# schematics.net
KiCad netlist of a schematic drawn in EAGLE
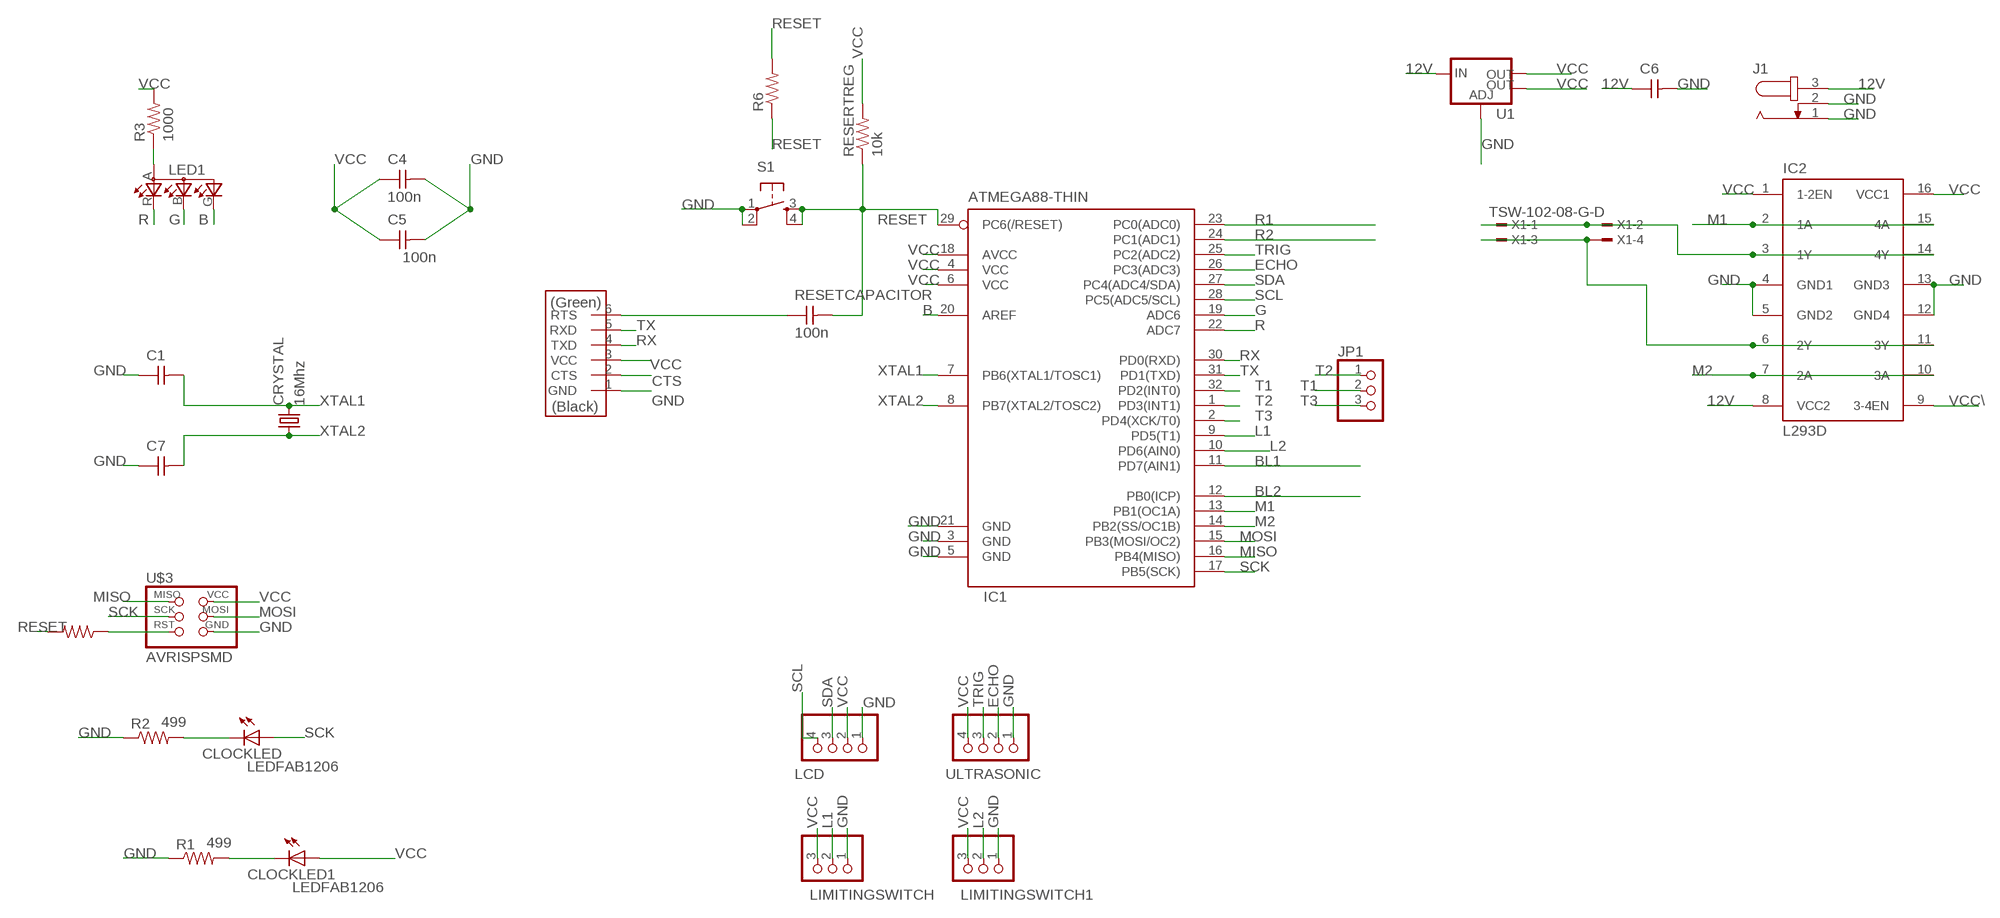
[diagram p0: schematic, sheet 1]

(export (version "E")
  (design (tool "Eeschema 10.0.6"))
  (components
    (comp (ref "C1")
      (value "CAP-UNPOLARIZEDFAB")
      (footprint "eagle-import:C1206FAB")
      (libsource (lib "eagle-import") (part "CAP-UNPOLARIZEDFAB"))
    )
    (comp (ref "C4")
      (value "100n")
      (footprint "eagle-import:C1206FAB")
      (libsource (lib "eagle-import") (part "CAP-UNPOLARIZEDFAB"))
    )
    (comp (ref "C5")
      (value "100n")
      (footprint "eagle-import:C1206FAB")
      (libsource (lib "eagle-import") (part "CAP-UNPOLARIZEDFAB"))
    )
    (comp (ref "C6")
      (value "CAP-UNPOLARIZEDFAB")
      (footprint "eagle-import:C1206FAB")
      (libsource (lib "eagle-import") (part "CAP-UNPOLARIZEDFAB"))
    )
    (comp (ref "C7")
      (value "CAP-UNPOLARIZEDFAB")
      (footprint "eagle-import:C1206FAB")
      (libsource (lib "eagle-import") (part "CAP-UNPOLARIZEDFAB"))
    )
    (comp (ref "CLOCKLED")
      (value "LEDFAB1206")
      (footprint "eagle-import:LED1206FAB")
      (libsource (lib "eagle-import") (part "LEDFAB1206"))
    )
    (comp (ref "CLOCKLED1")
      (value "LEDFAB1206")
      (footprint "eagle-import:LED1206FAB")
      (libsource (lib "eagle-import") (part "LEDFAB1206"))
    )
    (comp (ref "CRYSTAL")
      (value "16Mhz")
      (footprint "eagle-import:CSM-7X-DU")
      (libsource (lib "eagle-import") (part "CSM-7X-DU"))
    )
    (comp (ref "IC1")
      (value "ATMEGA88-THIN")
      (footprint "eagle-import:TQFP32-08THIN")
      (libsource (lib "eagle-import") (part "ATMEGA88-THIN"))
    )
    (comp (ref "IC2")
      (value "L293D")
      (footprint "eagle-import:DIL16")
      (libsource (lib "eagle-import") (part "L293D"))
    )
    (comp (ref "J1")
      (value "JACK-PLUG1")
      (footprint "eagle-import:SPC4078")
      (libsource (lib "eagle-import") (part "JACK-PLUG1"))
    )
    (comp (ref "JP1")
      (value "PINHD-1X31X03_SMT")
      (footprint "eagle-import:1X03_SMT")
      (libsource (lib "eagle-import") (part "PINHD-1X31X03_SMT"))
    )
    (comp (ref "LCD")
      (value "PINHD-1X41X04_SMT")
      (footprint "eagle-import:1X04_SMT")
      (libsource (lib "eagle-import") (part "PINHD-1X41X04_SMT"))
    )
    (comp (ref "LED1")
      (value "LEDRGBOLD")
      (footprint "eagle-import:P-LCC-4-3")
      (libsource (lib "eagle-import") (part "LEDRGBOLD"))
    )
    (comp (ref "LIMITINGSWITCH")
      (value "PINHD-1X31X03_SMT")
      (footprint "eagle-import:1X03_SMT")
      (libsource (lib "eagle-import") (part "PINHD-1X31X03_SMT"))
    )
    (comp (ref "LIMITINGSWITCH1")
      (value "PINHD-1X31X03_SMT")
      (footprint "eagle-import:1X03_SMT")
      (libsource (lib "eagle-import") (part "PINHD-1X31X03_SMT"))
    )
    (comp (ref "R1")
      (value "499")
      (footprint "eagle-import:R1206FAB")
      (libsource (lib "eagle-import") (part "RES-US1206FAB"))
    )
    (comp (ref "R2")
      (value "499")
      (footprint "eagle-import:R1206FAB")
      (libsource (lib "eagle-import") (part "RES-US1206FAB"))
    )
    (comp (ref "R3")
      (value "1000")
      (footprint "eagle-import:R1206FAB")
      (libsource (lib "eagle-import") (part "RES-US1206FAB"))
    )
    (comp (ref "R4")
      (value "1000")
      (footprint "eagle-import:R1206FAB")
      (libsource (lib "eagle-import") (part "RES-US1206FAB"))
    )
    (comp (ref "R6")
      (value "1000")
      (footprint "eagle-import:R1206FAB")
      (libsource (lib "eagle-import") (part "RES-US1206FAB"))
    )
    (comp (ref "RESERTREG")
      (value "10k")
      (footprint "eagle-import:R1206FAB")
      (libsource (lib "eagle-import") (part "RES-US1206FAB"))
    )
    (comp (ref "RESETCAPACITOR")
      (value "100n")
      (footprint "eagle-import:C1206FAB")
      (libsource (lib "eagle-import") (part "CAP-UNPOLARIZEDFAB"))
    )
    (comp (ref "S1")
      (value "6MM_SWITCH6MM_SWITCH")
      (footprint "eagle-import:6MM_SWITCH")
      (libsource (lib "eagle-import") (part "6MM_SWITCH6MM_SWITCH"))
    )
    (comp (ref "U$2")
      (value "FTDI-SMD-HEADER")
      (footprint "eagle-import:1X06SMD")
      (libsource (lib "eagle-import") (part "FTDI-SMD-HEADER"))
    )
    (comp (ref "U$3")
      (value "AVRISPSMD")
      (footprint "eagle-import:2X03SMD")
      (libsource (lib "eagle-import") (part "AVRISPSMD"))
    )
    (comp (ref "U1")
      (value "V_REG_LM1117SOT223")
      (footprint "eagle-import:SOT223")
      (libsource (lib "eagle-import") (part "V_REG_LM1117SOT223"))
    )
    (comp (ref "ULTRASONIC")
      (value "PINHD-1X41X04_SMT")
      (footprint "eagle-import:1X04_SMT")
      (libsource (lib "eagle-import") (part "PINHD-1X41X04_SMT"))
    )
    (comp (ref "X1")
      (value "TSW-102-08-G-D")
      (footprint "eagle-import:TSW-102-XX-G-D")
      (fields (field (name "MF") "Samtec Inc.") (field (name "MPN") "TSW-102-07-G-D"))
      (libsource (lib "eagle-import") (part "TSW-102--G-D08"))
    )
  )
  (nets
    (net (code "1") (name "/12V") (class "Default")
      (node (ref "C6") (pin "1") (pinfunction "1_1") (pintype "passive"))
      (node (ref "IC2") (pin "8") (pinfunction "VCC2_8") (pintype "power_in"))
      (node (ref "J1") (pin "3") (pinfunction "3_3") (pintype "passive"))
      (node (ref "U1") (pin "3") (pinfunction "IN_3") (pintype "input"))
    )
    (net (code "2") (name "/B") (class "Default")
      (node (ref "IC1") (pin "20") (pinfunction "AREF_20") (pintype "passive"))
      (node (ref "LED1") (pin "G") (pinfunction "CGREEN_G") (pintype "passive"))
    )
    (net (code "3") (name "/BL1") (class "Default")
      (node (ref "IC1") (pin "11") (pinfunction "PD7(AIN1)_11") (pintype "bidirectional"))
    )
    (net (code "4") (name "/BL2") (class "Default")
      (node (ref "IC1") (pin "12") (pinfunction "PB0(ICP)_12") (pintype "bidirectional"))
    )
    (net (code "5") (name "/CTS") (class "Default")
      (node (ref "U$2") (pin "2") (pinfunction "CTS_2") (pintype "bidirectional"))
    )
    (net (code "6") (name "/ECHO") (class "Default")
      (node (ref "IC1") (pin "26") (pinfunction "PC3(ADC3)_26") (pintype "bidirectional"))
      (node (ref "ULTRASONIC") (pin "2") (pinfunction "2_2") (pintype "passive"))
    )
    (net (code "7") (name "/G") (class "Default")
      (node (ref "IC1") (pin "19") (pinfunction "ADC6_19") (pintype "bidirectional"))
      (node (ref "LED1") (pin "B") (pinfunction "CBLUE_B") (pintype "passive"))
    )
    (net (code "8") (name "/GND") (class "Default")
      (node (ref "C1") (pin "1") (pinfunction "1_1") (pintype "passive"))
      (node (ref "C4") (pin "2") (pinfunction "2_2") (pintype "passive"))
      (node (ref "C5") (pin "2") (pinfunction "2_2") (pintype "passive"))
      (node (ref "C6") (pin "2") (pinfunction "2_2") (pintype "passive"))
      (node (ref "C7") (pin "1") (pinfunction "1_1") (pintype "passive"))
      (node (ref "IC1") (pin "21") (pinfunction "GND_21") (pintype "power_in"))
      (node (ref "IC1") (pin "3") (pinfunction "GND_3") (pintype "power_in"))
      (node (ref "IC1") (pin "5") (pinfunction "GND_5") (pintype "power_in"))
      (node (ref "IC2") (pin "12") (pinfunction "GND4_12") (pintype "power_in"))
      (node (ref "IC2") (pin "13") (pinfunction "GND3_13") (pintype "power_in"))
      (node (ref "IC2") (pin "4") (pinfunction "GND1_4") (pintype "power_in"))
      (node (ref "IC2") (pin "5") (pinfunction "GND2_5") (pintype "power_in"))
      (node (ref "J1") (pin "1") (pinfunction "1_1") (pintype "passive"))
      (node (ref "J1") (pin "2") (pinfunction "2_2") (pintype "passive"))
      (node (ref "LCD") (pin "1") (pinfunction "1_1") (pintype "passive"))
      (node (ref "LIMITINGSWITCH") (pin "1") (pinfunction "1_1") (pintype "passive"))
      (node (ref "LIMITINGSWITCH1") (pin "1") (pinfunction "1_1") (pintype "passive"))
      (node (ref "R1") (pin "1") (pinfunction "1_1") (pintype "passive"))
      (node (ref "R2") (pin "1") (pinfunction "1_1") (pintype "passive"))
      (node (ref "S1") (pin "1") (pinfunction "P_1") (pintype "passive"))
      (node (ref "S1") (pin "2") (pinfunction "P1_2") (pintype "passive"))
      (node (ref "U$2") (pin "1") (pinfunction "GND_1") (pintype "bidirectional"))
      (node (ref "U$3") (pin "6") (pinfunction "GND_6") (pintype "passive"))
      (node (ref "U1") (pin "1") (pinfunction "ADJ_1") (pintype "input"))
      (node (ref "ULTRASONIC") (pin "1") (pinfunction "1_1") (pintype "passive"))
    )
    (net (code "9") (name "/L1") (class "Default")
      (node (ref "IC1") (pin "9") (pinfunction "PD5(T1)_9") (pintype "bidirectional"))
      (node (ref "LIMITINGSWITCH") (pin "2") (pinfunction "2_2") (pintype "passive"))
    )
    (net (code "10") (name "/L2") (class "Default")
      (node (ref "IC1") (pin "10") (pinfunction "PD6(AIN0)_10") (pintype "bidirectional"))
      (node (ref "LIMITINGSWITCH1") (pin "2") (pinfunction "2_2") (pintype "passive"))
    )
    (net (code "11") (name "/M1") (class "Default")
      (node (ref "IC1") (pin "13") (pinfunction "PB1(OC1A)_13") (pintype "bidirectional"))
      (node (ref "IC2") (pin "15") (pinfunction "4A_15") (pintype "input"))
      (node (ref "IC2") (pin "2") (pinfunction "1A_2") (pintype "input"))
    )
    (net (code "12") (name "/M2") (class "Default")
      (node (ref "IC1") (pin "14") (pinfunction "PB2(SS/OC1B)_14") (pintype "bidirectional"))
      (node (ref "IC2") (pin "10") (pinfunction "3A_10") (pintype "input"))
      (node (ref "IC2") (pin "7") (pinfunction "2A_7") (pintype "input"))
    )
    (net (code "13") (name "/MISO") (class "Default")
      (node (ref "IC1") (pin "16") (pinfunction "PB4(MISO)_16") (pintype "bidirectional"))
      (node (ref "U$3") (pin "1") (pinfunction "MISO_1") (pintype "passive"))
    )
    (net (code "14") (name "/MOSI") (class "Default")
      (node (ref "IC1") (pin "15") (pinfunction "PB3(MOSI/OC2)_15") (pintype "bidirectional"))
      (node (ref "U$3") (pin "4") (pinfunction "MOSI_4") (pintype "passive"))
    )
    (net (code "15") (name "/R") (class "Default")
      (node (ref "IC1") (pin "22") (pinfunction "ADC7_22") (pintype "bidirectional"))
      (node (ref "LED1") (pin "R") (pinfunction "CRED_R") (pintype "passive"))
    )
    (net (code "16") (name "/R1") (class "Default")
      (node (ref "IC1") (pin "23") (pinfunction "PC0(ADC0)_23") (pintype "bidirectional"))
    )
    (net (code "17") (name "/R2") (class "Default")
      (node (ref "IC1") (pin "24") (pinfunction "PC1(ADC1)_24") (pintype "bidirectional"))
    )
    (net (code "18") (name "/RESET") (class "Default")
      (node (ref "IC1") (pin "29") (pinfunction "PC6(/RESET)_29") (pintype "bidirectional"))
      (node (ref "R4") (pin "2") (pinfunction "2_2") (pintype "passive"))
      (node (ref "R6") (pin "1") (pinfunction "1_1") (pintype "passive"))
      (node (ref "R6") (pin "2") (pinfunction "2_2") (pintype "passive"))
      (node (ref "RESERTREG") (pin "1") (pinfunction "1_1") (pintype "passive"))
      (node (ref "RESETCAPACITOR") (pin "2") (pinfunction "2_2") (pintype "passive"))
      (node (ref "S1") (pin "3") (pinfunction "S_3") (pintype "passive"))
      (node (ref "S1") (pin "4") (pinfunction "S1_4") (pintype "passive"))
    )
    (net (code "19") (name "/RX") (class "Default")
      (node (ref "IC1") (pin "30") (pinfunction "PD0(RXD)_30") (pintype "bidirectional"))
      (node (ref "U$2") (pin "4") (pinfunction "TXD_4") (pintype "bidirectional"))
    )
    (net (code "20") (name "/SCK") (class "Default")
      (node (ref "CLOCKLED") (pin "1") (pinfunction "A_1") (pintype "passive"))
      (node (ref "IC1") (pin "17") (pinfunction "PB5(SCK)_17") (pintype "bidirectional"))
      (node (ref "U$3") (pin "3") (pinfunction "SCK_3") (pintype "passive"))
    )
    (net (code "21") (name "/SCL") (class "Default")
      (node (ref "IC1") (pin "28") (pinfunction "PC5(ADC5/SCL)_28") (pintype "bidirectional"))
      (node (ref "LCD") (pin "4") (pinfunction "4_4") (pintype "passive"))
    )
    (net (code "22") (name "/SDA") (class "Default")
      (node (ref "IC1") (pin "27") (pinfunction "PC4(ADC4/SDA)_27") (pintype "bidirectional"))
      (node (ref "LCD") (pin "3") (pinfunction "3_3") (pintype "passive"))
    )
    (net (code "23") (name "/T1") (class "Default")
      (node (ref "IC1") (pin "32") (pinfunction "PD2(INT0)_32") (pintype "bidirectional"))
      (node (ref "JP1") (pin "2") (pinfunction "2_2") (pintype "passive"))
    )
    (net (code "24") (name "/T2") (class "Default")
      (node (ref "IC1") (pin "1") (pinfunction "PD3(INT1)_1") (pintype "bidirectional"))
      (node (ref "JP1") (pin "1") (pinfunction "1_1") (pintype "passive"))
    )
    (net (code "25") (name "/T3") (class "Default")
      (node (ref "IC1") (pin "2") (pinfunction "PD4(XCK/T0)_2") (pintype "bidirectional"))
      (node (ref "JP1") (pin "3") (pinfunction "3_3") (pintype "passive"))
    )
    (net (code "26") (name "/TRIG") (class "Default")
      (node (ref "IC1") (pin "25") (pinfunction "PC2(ADC2)_25") (pintype "bidirectional"))
      (node (ref "ULTRASONIC") (pin "3") (pinfunction "3_3") (pintype "passive"))
    )
    (net (code "27") (name "/TX") (class "Default")
      (node (ref "IC1") (pin "31") (pinfunction "PD1(TXD)_31") (pintype "bidirectional"))
      (node (ref "U$2") (pin "5") (pinfunction "RXD_5") (pintype "bidirectional"))
    )
    (net (code "28") (name "/VCC") (class "Default")
      (node (ref "C4") (pin "1") (pinfunction "1_1") (pintype "passive"))
      (node (ref "C5") (pin "1") (pinfunction "1_1") (pintype "passive"))
      (node (ref "CLOCKLED1") (pin "1") (pinfunction "A_1") (pintype "passive"))
      (node (ref "IC1") (pin "18") (pinfunction "AVCC_18") (pintype "power_in"))
      (node (ref "IC1") (pin "4") (pinfunction "VCC_4") (pintype "power_in"))
      (node (ref "IC1") (pin "6") (pinfunction "VCC_6") (pintype "power_in"))
      (node (ref "IC2") (pin "1") (pinfunction "1-2EN_1") (pintype "input"))
      (node (ref "IC2") (pin "16") (pinfunction "VCC1_16") (pintype "power_in"))
      (node (ref "LCD") (pin "2") (pinfunction "2_2") (pintype "passive"))
      (node (ref "LIMITINGSWITCH") (pin "3") (pinfunction "3_3") (pintype "passive"))
      (node (ref "LIMITINGSWITCH1") (pin "3") (pinfunction "3_3") (pintype "passive"))
      (node (ref "R3") (pin "2") (pinfunction "2_2") (pintype "passive"))
      (node (ref "RESERTREG") (pin "2") (pinfunction "2_2") (pintype "passive"))
      (node (ref "U$2") (pin "3") (pinfunction "VCC_3") (pintype "bidirectional"))
      (node (ref "U$3") (pin "2") (pinfunction "VCC_2") (pintype "passive"))
      (node (ref "U1") (pin "2") (pinfunction "OUT_2") (pintype "output"))
      (node (ref "U1") (pin "4") (pinfunction "OUT_4") (pintype "output"))
      (node (ref "ULTRASONIC") (pin "4") (pinfunction "4_4") (pintype "passive"))
    )
    (net (code "29") (name "/VCC\\") (class "Default")
      (node (ref "IC2") (pin "9") (pinfunction "3-4EN_9") (pintype "input"))
    )
    (net (code "30") (name "/XTAL1") (class "Default")
      (node (ref "C1") (pin "2") (pinfunction "2_2") (pintype "passive"))
      (node (ref "CRYSTAL") (pin "2") (pinfunction "2_2") (pintype "passive"))
      (node (ref "IC1") (pin "7") (pinfunction "PB6(XTAL1/TOSC1)_7") (pintype "bidirectional"))
    )
    (net (code "31") (name "/XTAL2") (class "Default")
      (node (ref "C7") (pin "2") (pinfunction "2_2") (pintype "passive"))
      (node (ref "CRYSTAL") (pin "1") (pinfunction "1_1") (pintype "passive"))
      (node (ref "IC1") (pin "8") (pinfunction "PB7(XTAL2/TOSC2)_8") (pintype "bidirectional"))
    )
    (net (code "32") (name "Net-(CLOCKLED-C)") (class "Default")
      (node (ref "CLOCKLED") (pin "2") (pinfunction "C_2") (pintype "passive"))
      (node (ref "R2") (pin "2") (pinfunction "2_2") (pintype "passive"))
    )
    (net (code "33") (name "Net-(CLOCKLED1-C)") (class "Default")
      (node (ref "CLOCKLED1") (pin "2") (pinfunction "C_2") (pintype "passive"))
      (node (ref "R1") (pin "2") (pinfunction "2_2") (pintype "passive"))
    )
    (net (code "34") (name "Net-(IC2-1Y)") (class "Default")
      (node (ref "IC2") (pin "14") (pinfunction "4Y_14") (pintype "output"))
      (node (ref "IC2") (pin "3") (pinfunction "1Y_3") (pintype "output"))
      (node (ref "X1") (pin "1") (pinfunction "1_1") (pintype "passive"))
      (node (ref "X1") (pin "2") (pinfunction "1_2") (pintype "passive"))
    )
    (net (code "35") (name "Net-(IC2-2Y)") (class "Default")
      (node (ref "IC2") (pin "11") (pinfunction "3Y_11") (pintype "output"))
      (node (ref "IC2") (pin "6") (pinfunction "2Y_6") (pintype "output"))
      (node (ref "X1") (pin "3") (pinfunction "1_3") (pintype "passive"))
      (node (ref "X1") (pin "4") (pinfunction "1_4") (pintype "passive"))
    )
    (net (code "36") (name "Net-(LED1-A2)") (class "Default")
      (node (ref "LED1") (pin "A") (pinfunction "A2_A") (pintype "passive"))
      (node (ref "R3") (pin "1") (pinfunction "1_1") (pintype "passive"))
    )
    (net (code "37") (name "Net-(U$2-RTS)") (class "Default")
      (node (ref "RESETCAPACITOR") (pin "1") (pinfunction "1_1") (pintype "passive"))
      (node (ref "U$2") (pin "6") (pinfunction "RTS_6") (pintype "bidirectional"))
    )
    (net (code "38") (name "Net-(U$3-RST)") (class "Default")
      (node (ref "R4") (pin "1") (pinfunction "1_1") (pintype "passive"))
      (node (ref "U$3") (pin "5") (pinfunction "RST_5") (pintype "passive"))
    )
  )
)
